# SwitchMatrix.net
KiCad netlist of a schematic drawn in Altium Designer
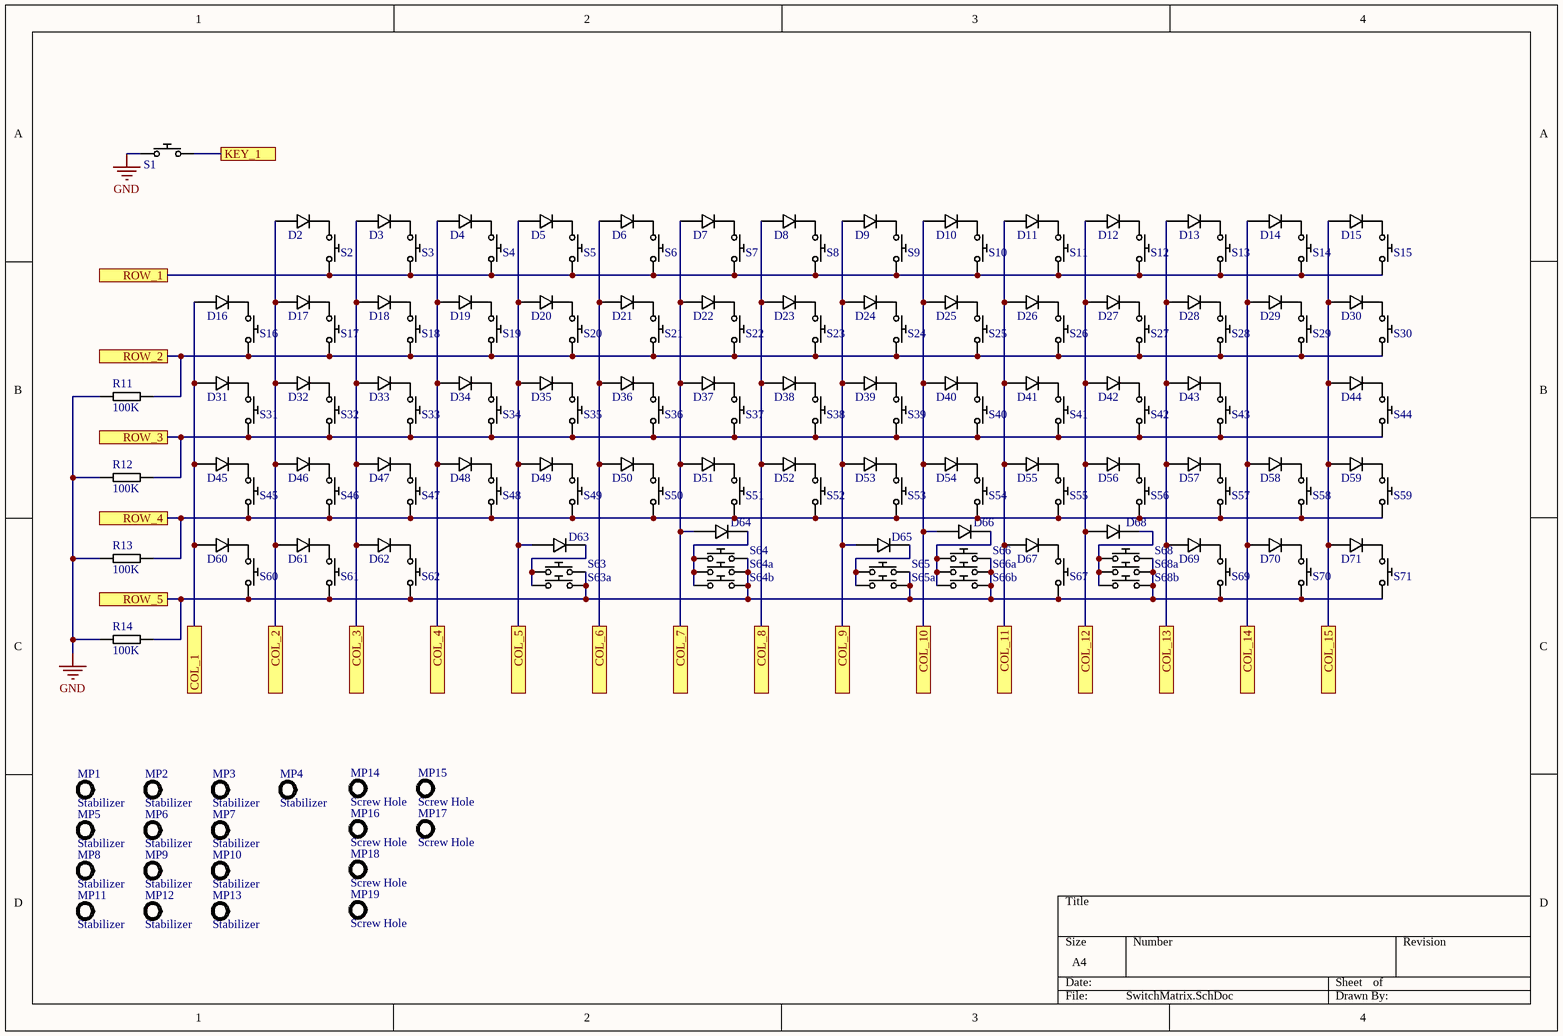
[diagram p0: SwitchMatrix.SchDoc]

(export (version "E")
  (design (tool "Eeschema 10.0.6"))
  (components
    (comp (ref "D2") (value "Diode") (footprint "SOD_323") (libsource (lib "NautilusKB") (part "Diode")))
    (comp (ref "D3") (value "Diode") (footprint "SOD_323") (libsource (lib "NautilusKB") (part "Diode")))
    (comp (ref "D4") (value "Diode") (footprint "SOD_323") (libsource (lib "NautilusKB") (part "Diode")))
    (comp (ref "D5") (value "Diode") (footprint "SOD_323") (libsource (lib "NautilusKB") (part "Diode")))
    (comp (ref "D6") (value "Diode") (footprint "SOD_323") (libsource (lib "NautilusKB") (part "Diode")))
    (comp (ref "D7") (value "Diode") (footprint "SOD_323") (libsource (lib "NautilusKB") (part "Diode")))
    (comp (ref "D8") (value "Diode") (footprint "SOD_323") (libsource (lib "NautilusKB") (part "Diode")))
    (comp (ref "D9") (value "Diode") (footprint "SOD_323") (libsource (lib "NautilusKB") (part "Diode")))
    (comp (ref "D10") (value "Diode") (footprint "SOD_323") (libsource (lib "NautilusKB") (part "Diode")))
    (comp (ref "D11") (value "Diode") (footprint "SOD_323") (libsource (lib "NautilusKB") (part "Diode")))
    (comp (ref "D12") (value "Diode") (footprint "SOD_323") (libsource (lib "NautilusKB") (part "Diode")))
    (comp (ref "D13") (value "Diode") (footprint "SOD_323") (libsource (lib "NautilusKB") (part "Diode")))
    (comp (ref "D14") (value "Diode") (footprint "SOD_323") (libsource (lib "NautilusKB") (part "Diode")))
    (comp (ref "D15") (value "Diode") (footprint "SOD_323") (libsource (lib "NautilusKB") (part "Diode")))
    (comp (ref "D16") (value "Diode") (footprint "SOD_323") (libsource (lib "NautilusKB") (part "Diode")))
    (comp (ref "D17") (value "Diode") (footprint "SOD_323") (libsource (lib "NautilusKB") (part "Diode")))
    (comp (ref "D18") (value "Diode") (footprint "SOD_323") (libsource (lib "NautilusKB") (part "Diode")))
    (comp (ref "D19") (value "Diode") (footprint "SOD_323") (libsource (lib "NautilusKB") (part "Diode")))
    (comp (ref "D20") (value "Diode") (footprint "SOD_323") (libsource (lib "NautilusKB") (part "Diode")))
    (comp (ref "D21") (value "Diode") (footprint "SOD_323") (libsource (lib "NautilusKB") (part "Diode")))
    (comp (ref "D22") (value "Diode") (footprint "SOD_323") (libsource (lib "NautilusKB") (part "Diode")))
    (comp (ref "D23") (value "Diode") (footprint "SOD_323") (libsource (lib "NautilusKB") (part "Diode")))
    (comp (ref "D24") (value "Diode") (footprint "SOD_323") (libsource (lib "NautilusKB") (part "Diode")))
    (comp (ref "D25") (value "Diode") (footprint "SOD_323") (libsource (lib "NautilusKB") (part "Diode")))
    (comp (ref "D26") (value "Diode") (footprint "SOD_323") (libsource (lib "NautilusKB") (part "Diode")))
    (comp (ref "D27") (value "Diode") (footprint "SOD_323") (libsource (lib "NautilusKB") (part "Diode")))
    (comp (ref "D28") (value "Diode") (footprint "SOD_323") (libsource (lib "NautilusKB") (part "Diode")))
    (comp (ref "D29") (value "Diode") (footprint "SOD_323") (libsource (lib "NautilusKB") (part "Diode")))
    (comp (ref "D30") (value "Diode") (footprint "SOD_323") (libsource (lib "NautilusKB") (part "Diode")))
    (comp (ref "D31") (value "Diode") (footprint "SOD_323") (libsource (lib "NautilusKB") (part "Diode")))
    (comp (ref "D32") (value "Diode") (footprint "SOD_323") (libsource (lib "NautilusKB") (part "Diode")))
    (comp (ref "D33") (value "Diode") (footprint "SOD_323") (libsource (lib "NautilusKB") (part "Diode")))
    (comp (ref "D34") (value "Diode") (footprint "SOD_323") (libsource (lib "NautilusKB") (part "Diode")))
    (comp (ref "D35") (value "Diode") (footprint "SOD_323") (libsource (lib "NautilusKB") (part "Diode")))
    (comp (ref "D36") (value "Diode") (footprint "SOD_323") (libsource (lib "NautilusKB") (part "Diode")))
    (comp (ref "D37") (value "Diode") (footprint "SOD_323") (libsource (lib "NautilusKB") (part "Diode")))
    (comp (ref "D38") (value "Diode") (footprint "SOD_323") (libsource (lib "NautilusKB") (part "Diode")))
    (comp (ref "D39") (value "Diode") (footprint "SOD_323") (libsource (lib "NautilusKB") (part "Diode")))
    (comp (ref "D40") (value "Diode") (footprint "SOD_323") (libsource (lib "NautilusKB") (part "Diode")))
    (comp (ref "D41") (value "Diode") (footprint "SOD_323") (libsource (lib "NautilusKB") (part "Diode")))
    (comp (ref "D42") (value "Diode") (footprint "SOD_323") (libsource (lib "NautilusKB") (part "Diode")))
    (comp (ref "D43") (value "Diode") (footprint "SOD_323") (libsource (lib "NautilusKB") (part "Diode")))
    (comp (ref "D44") (value "Diode") (footprint "SOD_323") (libsource (lib "NautilusKB") (part "Diode")))
    (comp (ref "D45") (value "Diode") (footprint "SOD_323") (libsource (lib "NautilusKB") (part "Diode")))
    (comp (ref "D46") (value "Diode") (footprint "SOD_323") (libsource (lib "NautilusKB") (part "Diode")))
    (comp (ref "D47") (value "Diode") (footprint "SOD_323") (libsource (lib "NautilusKB") (part "Diode")))
    (comp (ref "D48") (value "Diode") (footprint "SOD_323") (libsource (lib "NautilusKB") (part "Diode")))
    (comp (ref "D49") (value "Diode") (footprint "SOD_323") (libsource (lib "NautilusKB") (part "Diode")))
    (comp (ref "D50") (value "Diode") (footprint "SOD_323") (libsource (lib "NautilusKB") (part "Diode")))
    (comp (ref "D51") (value "Diode") (footprint "SOD_323") (libsource (lib "NautilusKB") (part "Diode")))
    (comp (ref "D52") (value "Diode") (footprint "SOD_323") (libsource (lib "NautilusKB") (part "Diode")))
    (comp (ref "D53") (value "Diode") (footprint "SOD_323") (libsource (lib "NautilusKB") (part "Diode")))
    (comp (ref "D54") (value "Diode") (footprint "SOD_323") (libsource (lib "NautilusKB") (part "Diode")))
    (comp (ref "D55") (value "Diode") (footprint "SOD_323") (libsource (lib "NautilusKB") (part "Diode")))
    (comp (ref "D56") (value "Diode") (footprint "SOD_323") (libsource (lib "NautilusKB") (part "Diode")))
    (comp (ref "D57") (value "Diode") (footprint "SOD_323") (libsource (lib "NautilusKB") (part "Diode")))
    (comp (ref "D58") (value "Diode") (footprint "SOD_323") (libsource (lib "NautilusKB") (part "Diode")))
    (comp (ref "D59") (value "Diode") (footprint "SOD_323") (libsource (lib "NautilusKB") (part "Diode")))
    (comp (ref "D60") (value "Diode") (footprint "SOD_323") (libsource (lib "NautilusKB") (part "Diode")))
    (comp (ref "D61") (value "Diode") (footprint "SOD_323") (libsource (lib "NautilusKB") (part "Diode")))
    (comp (ref "D62") (value "Diode") (footprint "SOD_323") (libsource (lib "NautilusKB") (part "Diode")))
    (comp (ref "D63") (value "Diode") (footprint "SOD_323") (libsource (lib "NautilusKB") (part "Diode")))
    (comp (ref "D64") (value "Diode") (footprint "SOD_323") (libsource (lib "NautilusKB") (part "Diode")))
    (comp (ref "D65") (value "Diode") (footprint "SOD_323") (libsource (lib "NautilusKB") (part "Diode")))
    (comp (ref "D66") (value "Diode") (footprint "SOD_323") (libsource (lib "NautilusKB") (part "Diode")))
    (comp (ref "D67") (value "Diode") (footprint "SOD_323") (libsource (lib "NautilusKB") (part "Diode")))
    (comp (ref "D68") (value "Diode") (footprint "SOD_323") (libsource (lib "NautilusKB") (part "Diode")))
    (comp (ref "D69") (value "Diode") (footprint "SOD_323") (libsource (lib "NautilusKB") (part "Diode")))
    (comp (ref "D70") (value "Diode") (footprint "SOD_323") (libsource (lib "NautilusKB") (part "Diode")))
    (comp (ref "D71") (value "Diode") (footprint "SOD_323") (libsource (lib "NautilusKB") (part "Diode")))
    (comp (ref "MP1")
      (value "Stabilizer")
      (footprint "Cherry_stabilizer")
      (libsource (lib "NautilusKB") (part "Cherry_Stabilizer"))
    )
    (comp (ref "MP2")
      (value "Stabilizer")
      (footprint "Cherry_stabilizer")
      (libsource (lib "NautilusKB") (part "Cherry_Stabilizer"))
    )
    (comp (ref "MP3")
      (value "Stabilizer")
      (footprint "Cherry_stabilizer")
      (libsource (lib "NautilusKB") (part "Cherry_Stabilizer"))
    )
    (comp (ref "MP4")
      (value "Stabilizer")
      (footprint "Cherry_stabilizer")
      (libsource (lib "NautilusKB") (part "Cherry_Stabilizer"))
    )
    (comp (ref "MP5")
      (value "Stabilizer")
      (footprint "Cherry_stabilizer")
      (libsource (lib "NautilusKB") (part "Cherry_Stabilizer"))
    )
    (comp (ref "MP6")
      (value "Stabilizer")
      (footprint "Cherry_stabilizer")
      (libsource (lib "NautilusKB") (part "Cherry_Stabilizer"))
    )
    (comp (ref "MP7")
      (value "Stabilizer")
      (footprint "Cherry_stabilizer")
      (libsource (lib "NautilusKB") (part "Cherry_Stabilizer"))
    )
    (comp (ref "MP8")
      (value "Stabilizer")
      (footprint "Cherry_stabilizer")
      (libsource (lib "NautilusKB") (part "Cherry_Stabilizer"))
    )
    (comp (ref "MP9")
      (value "Stabilizer")
      (footprint "Cherry_stabilizer")
      (libsource (lib "NautilusKB") (part "Cherry_Stabilizer"))
    )
    (comp (ref "MP10")
      (value "Stabilizer")
      (footprint "Cherry_stabilizer")
      (libsource (lib "NautilusKB") (part "Cherry_Stabilizer"))
    )
    (comp (ref "MP11")
      (value "Stabilizer")
      (footprint "Cherry_stabilizer")
      (libsource (lib "NautilusKB") (part "Cherry_Stabilizer"))
    )
    (comp (ref "MP12")
      (value "Stabilizer")
      (footprint "Cherry_stabilizer")
      (libsource (lib "NautilusKB") (part "Cherry_Stabilizer"))
    )
    (comp (ref "MP13")
      (value "Stabilizer")
      (footprint "Cherry_stabilizer")
      (libsource (lib "NautilusKB") (part "Cherry_Stabilizer"))
    )
    (comp (ref "MP14")
      (value "Screw Hole")
      (footprint "Slot_2.2x5mm")
      (libsource (lib "NautilusKB") (part "Mechanical_part"))
    )
    (comp (ref "MP15")
      (value "Screw Hole")
      (footprint "Slot_2.2x5mm")
      (libsource (lib "NautilusKB") (part "Mechanical_part"))
    )
    (comp (ref "MP16")
      (value "Screw Hole")
      (footprint "Slot_2.2x5mm")
      (libsource (lib "NautilusKB") (part "Mechanical_part"))
    )
    (comp (ref "MP17")
      (value "Screw Hole")
      (footprint "Slot_2.2x5mm")
      (libsource (lib "NautilusKB") (part "Mechanical_part"))
    )
    (comp (ref "MP18")
      (value "Screw Hole")
      (footprint "Slot_2.2x5mm")
      (libsource (lib "NautilusKB") (part "Mechanical_part"))
    )
    (comp (ref "MP19")
      (value "Screw Hole")
      (footprint "Slot_2.2x5mm")
      (libsource (lib "NautilusKB") (part "Mechanical_part"))
    )
    (comp (ref "R11")
      (value "100K")
      (footprint "Resistor_0603")
      (libsource (lib "NautilusKB") (part "Resistor"))
    )
    (comp (ref "R12")
      (value "100K")
      (footprint "Resistor_0603")
      (libsource (lib "NautilusKB") (part "Resistor"))
    )
    (comp (ref "R13")
      (value "100K")
      (footprint "Resistor_0603")
      (libsource (lib "NautilusKB") (part "Resistor"))
    )
    (comp (ref "R14")
      (value "100K")
      (footprint "Resistor_0603")
      (libsource (lib "NautilusKB") (part "Resistor"))
    )
    (comp (ref "S1")
      (value "Pushbutton_2P")
      (footprint "CherryMX_PCB_RGB")
      (libsource (lib "NautilusKB") (part "Pushbutton_2P"))
    )
    (comp (ref "S2")
      (value "Pushbutton_2P")
      (footprint "CherryMX_PCB_RGB")
      (libsource (lib "NautilusKB") (part "Pushbutton_2P"))
    )
    (comp (ref "S3")
      (value "Pushbutton_2P")
      (footprint "CherryMX_PCB_RGB")
      (libsource (lib "NautilusKB") (part "Pushbutton_2P"))
    )
    (comp (ref "S4")
      (value "Pushbutton_2P")
      (footprint "CherryMX_PCB_RGB")
      (libsource (lib "NautilusKB") (part "Pushbutton_2P"))
    )
    (comp (ref "S5")
      (value "Pushbutton_2P")
      (footprint "CherryMX_PCB_RGB")
      (libsource (lib "NautilusKB") (part "Pushbutton_2P"))
    )
    (comp (ref "S6")
      (value "Pushbutton_2P")
      (footprint "CherryMX_PCB_RGB")
      (libsource (lib "NautilusKB") (part "Pushbutton_2P"))
    )
    (comp (ref "S7")
      (value "Pushbutton_2P")
      (footprint "CherryMX_PCB_RGB")
      (libsource (lib "NautilusKB") (part "Pushbutton_2P"))
    )
    (comp (ref "S8")
      (value "Pushbutton_2P")
      (footprint "CherryMX_PCB_RGB")
      (libsource (lib "NautilusKB") (part "Pushbutton_2P"))
    )
    (comp (ref "S9")
      (value "Pushbutton_2P")
      (footprint "CherryMX_PCB_RGB")
      (libsource (lib "NautilusKB") (part "Pushbutton_2P"))
    )
    (comp (ref "S10")
      (value "Pushbutton_2P")
      (footprint "CherryMX_PCB_RGB")
      (libsource (lib "NautilusKB") (part "Pushbutton_2P"))
    )
    (comp (ref "S11")
      (value "Pushbutton_2P")
      (footprint "CherryMX_PCB_RGB")
      (libsource (lib "NautilusKB") (part "Pushbutton_2P"))
    )
    (comp (ref "S12")
      (value "Pushbutton_2P")
      (footprint "CherryMX_PCB_RGB")
      (libsource (lib "NautilusKB") (part "Pushbutton_2P"))
    )
    (comp (ref "S13")
      (value "Pushbutton_2P")
      (footprint "CherryMX_PCB_RGB")
      (libsource (lib "NautilusKB") (part "Pushbutton_2P"))
    )
    (comp (ref "S14")
      (value "Pushbutton_2P")
      (footprint "CherryMX_PCB_RGB")
      (libsource (lib "NautilusKB") (part "Pushbutton_2P"))
    )
    (comp (ref "S15")
      (value "Pushbutton_2P")
      (footprint "CherryMX_PCB_RGB")
      (libsource (lib "NautilusKB") (part "Pushbutton_2P"))
    )
    (comp (ref "S16")
      (value "Pushbutton_2P")
      (footprint "CherryMX_PCB_RGB")
      (libsource (lib "NautilusKB") (part "Pushbutton_2P"))
    )
    (comp (ref "S17")
      (value "Pushbutton_2P")
      (footprint "CherryMX_PCB_RGB")
      (libsource (lib "NautilusKB") (part "Pushbutton_2P"))
    )
    (comp (ref "S18")
      (value "Pushbutton_2P")
      (footprint "CherryMX_PCB_RGB")
      (libsource (lib "NautilusKB") (part "Pushbutton_2P"))
    )
    (comp (ref "S19")
      (value "Pushbutton_2P")
      (footprint "CherryMX_PCB_RGB")
      (libsource (lib "NautilusKB") (part "Pushbutton_2P"))
    )
    (comp (ref "S20")
      (value "Pushbutton_2P")
      (footprint "CherryMX_PCB_RGB")
      (libsource (lib "NautilusKB") (part "Pushbutton_2P"))
    )
    (comp (ref "S21")
      (value "Pushbutton_2P")
      (footprint "CherryMX_PCB_RGB")
      (libsource (lib "NautilusKB") (part "Pushbutton_2P"))
    )
    (comp (ref "S22")
      (value "Pushbutton_2P")
      (footprint "CherryMX_PCB_RGB")
      (libsource (lib "NautilusKB") (part "Pushbutton_2P"))
    )
    (comp (ref "S23")
      (value "Pushbutton_2P")
      (footprint "CherryMX_PCB_RGB")
      (libsource (lib "NautilusKB") (part "Pushbutton_2P"))
    )
    (comp (ref "S24")
      (value "Pushbutton_2P")
      (footprint "CherryMX_PCB_RGB")
      (libsource (lib "NautilusKB") (part "Pushbutton_2P"))
    )
    (comp (ref "S25")
      (value "Pushbutton_2P")
      (footprint "CherryMX_PCB_RGB")
      (libsource (lib "NautilusKB") (part "Pushbutton_2P"))
    )
    (comp (ref "S26")
      (value "Pushbutton_2P")
      (footprint "CherryMX_PCB_RGB")
      (libsource (lib "NautilusKB") (part "Pushbutton_2P"))
    )
    (comp (ref "S27")
      (value "Pushbutton_2P")
      (footprint "CherryMX_PCB_RGB")
      (libsource (lib "NautilusKB") (part "Pushbutton_2P"))
    )
    (comp (ref "S28")
      (value "Pushbutton_2P")
      (footprint "CherryMX_PCB_RGB")
      (libsource (lib "NautilusKB") (part "Pushbutton_2P"))
    )
    (comp (ref "S29")
      (value "Pushbutton_2P")
      (footprint "CherryMX_PCB_RGB")
      (libsource (lib "NautilusKB") (part "Pushbutton_2P"))
    )
    (comp (ref "S30")
      (value "Pushbutton_2P")
      (footprint "CherryMX_PCB_RGB")
      (libsource (lib "NautilusKB") (part "Pushbutton_2P"))
    )
    (comp (ref "S31")
      (value "Pushbutton_2P")
      (footprint "CherryMX_PCB_RGB")
      (libsource (lib "NautilusKB") (part "Pushbutton_2P"))
    )
    (comp (ref "S32")
      (value "Pushbutton_2P")
      (footprint "CherryMX_PCB_RGB")
      (libsource (lib "NautilusKB") (part "Pushbutton_2P"))
    )
    (comp (ref "S33")
      (value "Pushbutton_2P")
      (footprint "CherryMX_PCB_RGB")
      (libsource (lib "NautilusKB") (part "Pushbutton_2P"))
    )
    (comp (ref "S34")
      (value "Pushbutton_2P")
      (footprint "CherryMX_PCB_RGB")
      (libsource (lib "NautilusKB") (part "Pushbutton_2P"))
    )
    (comp (ref "S35")
      (value "Pushbutton_2P")
      (footprint "CherryMX_PCB_RGB")
      (libsource (lib "NautilusKB") (part "Pushbutton_2P"))
    )
    (comp (ref "S36")
      (value "Pushbutton_2P")
      (footprint "CherryMX_PCB_RGB")
      (libsource (lib "NautilusKB") (part "Pushbutton_2P"))
    )
    (comp (ref "S37")
      (value "Pushbutton_2P")
      (footprint "CherryMX_PCB_RGB")
      (libsource (lib "NautilusKB") (part "Pushbutton_2P"))
    )
    (comp (ref "S38")
      (value "Pushbutton_2P")
      (footprint "CherryMX_PCB_RGB")
      (libsource (lib "NautilusKB") (part "Pushbutton_2P"))
    )
    (comp (ref "S39")
      (value "Pushbutton_2P")
      (footprint "CherryMX_PCB_RGB")
      (libsource (lib "NautilusKB") (part "Pushbutton_2P"))
    )
    (comp (ref "S40")
      (value "Pushbutton_2P")
      (footprint "CherryMX_PCB_RGB")
      (libsource (lib "NautilusKB") (part "Pushbutton_2P"))
    )
    (comp (ref "S41")
      (value "Pushbutton_2P")
      (footprint "CherryMX_PCB_RGB")
      (libsource (lib "NautilusKB") (part "Pushbutton_2P"))
    )
    (comp (ref "S42")
      (value "Pushbutton_2P")
      (footprint "CherryMX_PCB_RGB")
      (libsource (lib "NautilusKB") (part "Pushbutton_2P"))
    )
    (comp (ref "S43")
      (value "Pushbutton_2P")
      (footprint "CherryMX_PCB_RGB")
      (libsource (lib "NautilusKB") (part "Pushbutton_2P"))
    )
    (comp (ref "S44")
      (value "Pushbutton_2P")
      (footprint "CherryMX_PCB_RGB")
      (libsource (lib "NautilusKB") (part "Pushbutton_2P"))
    )
    (comp (ref "S45")
      (value "Pushbutton_2P")
      (footprint "CherryMX_PCB_RGB")
      (libsource (lib "NautilusKB") (part "Pushbutton_2P"))
    )
    (comp (ref "S46")
      (value "Pushbutton_2P")
      (footprint "CherryMX_PCB_RGB")
      (libsource (lib "NautilusKB") (part "Pushbutton_2P"))
    )
    (comp (ref "S47")
      (value "Pushbutton_2P")
      (footprint "CherryMX_PCB_RGB")
      (libsource (lib "NautilusKB") (part "Pushbutton_2P"))
    )
    (comp (ref "S48")
      (value "Pushbutton_2P")
      (footprint "CherryMX_PCB_RGB")
      (libsource (lib "NautilusKB") (part "Pushbutton_2P"))
    )
    (comp (ref "S49")
      (value "Pushbutton_2P")
      (footprint "CherryMX_PCB_RGB")
      (libsource (lib "NautilusKB") (part "Pushbutton_2P"))
    )
    (comp (ref "S50")
      (value "Pushbutton_2P")
      (footprint "CherryMX_PCB_RGB")
      (libsource (lib "NautilusKB") (part "Pushbutton_2P"))
    )
    (comp (ref "S51")
      (value "Pushbutton_2P")
      (footprint "CherryMX_PCB_RGB")
      (libsource (lib "NautilusKB") (part "Pushbutton_2P"))
    )
    (comp (ref "S52")
      (value "Pushbutton_2P")
      (footprint "CherryMX_PCB_RGB")
      (libsource (lib "NautilusKB") (part "Pushbutton_2P"))
    )
    (comp (ref "S53")
      (value "Pushbutton_2P")
      (footprint "CherryMX_PCB_RGB")
      (libsource (lib "NautilusKB") (part "Pushbutton_2P"))
    )
    (comp (ref "S54")
      (value "Pushbutton_2P")
      (footprint "CherryMX_PCB_RGB")
      (libsource (lib "NautilusKB") (part "Pushbutton_2P"))
    )
    (comp (ref "S55")
      (value "Pushbutton_2P")
      (footprint "CherryMX_PCB_RGB")
      (libsource (lib "NautilusKB") (part "Pushbutton_2P"))
    )
    (comp (ref "S56")
      (value "Pushbutton_2P")
      (footprint "CherryMX_PCB_RGB")
      (libsource (lib "NautilusKB") (part "Pushbutton_2P"))
    )
    (comp (ref "S57")
      (value "Pushbutton_2P")
      (footprint "CherryMX_PCB_RGB")
      (libsource (lib "NautilusKB") (part "Pushbutton_2P"))
    )
    (comp (ref "S58")
      (value "Pushbutton_2P")
      (footprint "CherryMX_PCB_RGB")
      (libsource (lib "NautilusKB") (part "Pushbutton_2P"))
    )
    (comp (ref "S59")
      (value "Pushbutton_2P")
      (footprint "CherryMX_PCB_RGB")
      (libsource (lib "NautilusKB") (part "Pushbutton_2P"))
    )
    (comp (ref "S60")
      (value "Pushbutton_2P")
      (footprint "CherryMX_PCB_RGB")
      (libsource (lib "NautilusKB") (part "Pushbutton_2P"))
    )
    (comp (ref "S61")
      (value "Pushbutton_2P")
      (footprint "CherryMX_PCB_RGB")
      (libsource (lib "NautilusKB") (part "Pushbutton_2P"))
    )
    (comp (ref "S62")
      (value "Pushbutton_2P")
      (footprint "CherryMX_PCB_RGB")
      (libsource (lib "NautilusKB") (part "Pushbutton_2P"))
    )
    (comp (ref "S63")
      (value "Pushbutton_2P")
      (footprint "CherryMX_PCB_RGB")
      (libsource (lib "NautilusKB") (part "Pushbutton_2P"))
    )
    (comp (ref "S63a")
      (value "Pushbutton_2P")
      (footprint "CherryMX_PCB_RGB")
      (libsource (lib "NautilusKB") (part "Pushbutton_2P"))
    )
    (comp (ref "S64")
      (value "Pushbutton_2P")
      (footprint "CherryMX_PCB_RGB")
      (libsource (lib "NautilusKB") (part "Pushbutton_2P"))
    )
    (comp (ref "S64a")
      (value "Comment")
      (footprint "CherryMX_PCB_RGB")
      (libsource (lib "NautilusKB") (part "Pushbutton_2P"))
    )
    (comp (ref "S64b")
      (value "Comment")
      (footprint "CherryMX_PCB_RGB")
      (libsource (lib "NautilusKB") (part "Pushbutton_2P"))
    )
    (comp (ref "S65")
      (value "Pushbutton_2P")
      (footprint "CherryMX_PCB_RGB")
      (libsource (lib "NautilusKB") (part "Pushbutton_2P"))
    )
    (comp (ref "S65a")
      (value "Comment")
      (footprint "CherryMX_PCB_RGB")
      (libsource (lib "NautilusKB") (part "Pushbutton_2P"))
    )
    (comp (ref "S66")
      (value "Pushbutton_2P")
      (footprint "CherryMX_PCB_RGB")
      (libsource (lib "NautilusKB") (part "Pushbutton_2P"))
    )
    (comp (ref "S66a")
      (value "Comment")
      (footprint "CherryMX_PCB_RGB")
      (libsource (lib "NautilusKB") (part "Pushbutton_2P"))
    )
    (comp (ref "S66b")
      (value "Comment")
      (footprint "CherryMX_PCB_RGB")
      (libsource (lib "NautilusKB") (part "Pushbutton_2P"))
    )
    (comp (ref "S67")
      (value "Comment")
      (footprint "CherryMX_PCB_RGB")
      (libsource (lib "NautilusKB") (part "Pushbutton_2P"))
    )
    (comp (ref "S68")
      (value "Pushbutton_2P")
      (footprint "CherryMX_PCB_RGB")
      (libsource (lib "NautilusKB") (part "Pushbutton_2P"))
    )
    (comp (ref "S68a")
      (value "Comment")
      (footprint "CherryMX_PCB_RGB")
      (libsource (lib "NautilusKB") (part "Pushbutton_2P"))
    )
    (comp (ref "S68b")
      (value "Comment")
      (footprint "CherryMX_PCB_RGB")
      (libsource (lib "NautilusKB") (part "Pushbutton_2P"))
    )
    (comp (ref "S69")
      (value "Pushbutton_2P")
      (footprint "CherryMX_PCB_RGB")
      (libsource (lib "NautilusKB") (part "Pushbutton_2P"))
    )
    (comp (ref "S70")
      (value "Pushbutton_2P")
      (footprint "CherryMX_PCB_RGB")
      (libsource (lib "NautilusKB") (part "Pushbutton_2P"))
    )
    (comp (ref "S71")
      (value "Pushbutton_2P")
      (footprint "CherryMX_PCB_RGB")
      (libsource (lib "NautilusKB") (part "Pushbutton_2P"))
    )
  )
  (nets
    (net (code "1") (name "/COL_1") (class "Default")
      (node (ref "D16") (pin "A") (pintype "passive"))
      (node (ref "D31") (pin "A") (pintype "passive"))
      (node (ref "D45") (pin "A") (pintype "passive"))
      (node (ref "D60") (pin "A") (pintype "passive"))
    )
    (net (code "2") (name "/COL_2") (class "Default")
      (node (ref "D17") (pin "A") (pintype "passive"))
      (node (ref "D2") (pin "A") (pintype "passive"))
      (node (ref "D32") (pin "A") (pintype "passive"))
      (node (ref "D46") (pin "A") (pintype "passive"))
      (node (ref "D61") (pin "A") (pintype "passive"))
    )
    (net (code "3") (name "/COL_3") (class "Default")
      (node (ref "D18") (pin "A") (pintype "passive"))
      (node (ref "D3") (pin "A") (pintype "passive"))
      (node (ref "D33") (pin "A") (pintype "passive"))
      (node (ref "D47") (pin "A") (pintype "passive"))
      (node (ref "D62") (pin "A") (pintype "passive"))
    )
    (net (code "4") (name "/COL_4") (class "Default")
      (node (ref "D19") (pin "A") (pintype "passive"))
      (node (ref "D34") (pin "A") (pintype "passive"))
      (node (ref "D4") (pin "A") (pintype "passive"))
      (node (ref "D48") (pin "A") (pintype "passive"))
    )
    (net (code "5") (name "/COL_5") (class "Default")
      (node (ref "D20") (pin "A") (pintype "passive"))
      (node (ref "D35") (pin "A") (pintype "passive"))
      (node (ref "D49") (pin "A") (pintype "passive"))
      (node (ref "D5") (pin "A") (pintype "passive"))
      (node (ref "D63") (pin "A") (pintype "passive"))
    )
    (net (code "6") (name "/COL_6") (class "Default")
      (node (ref "D21") (pin "A") (pintype "passive"))
      (node (ref "D36") (pin "A") (pintype "passive"))
      (node (ref "D50") (pin "A") (pintype "passive"))
      (node (ref "D6") (pin "A") (pintype "passive"))
    )
    (net (code "7") (name "/COL_7") (class "Default")
      (node (ref "D22") (pin "A") (pintype "passive"))
      (node (ref "D37") (pin "A") (pintype "passive"))
      (node (ref "D51") (pin "A") (pintype "passive"))
      (node (ref "D64") (pin "A") (pintype "passive"))
      (node (ref "D7") (pin "A") (pintype "passive"))
    )
    (net (code "8") (name "/COL_8") (class "Default")
      (node (ref "D23") (pin "A") (pintype "passive"))
      (node (ref "D38") (pin "A") (pintype "passive"))
      (node (ref "D52") (pin "A") (pintype "passive"))
      (node (ref "D8") (pin "A") (pintype "passive"))
    )
    (net (code "9") (name "/COL_9") (class "Default")
      (node (ref "D24") (pin "A") (pintype "passive"))
      (node (ref "D39") (pin "A") (pintype "passive"))
      (node (ref "D53") (pin "A") (pintype "passive"))
      (node (ref "D65") (pin "A") (pintype "passive"))
      (node (ref "D9") (pin "A") (pintype "passive"))
    )
    (net (code "10") (name "/COL_10") (class "Default")
      (node (ref "D10") (pin "A") (pintype "passive"))
      (node (ref "D25") (pin "A") (pintype "passive"))
      (node (ref "D40") (pin "A") (pintype "passive"))
      (node (ref "D54") (pin "A") (pintype "passive"))
      (node (ref "D66") (pin "A") (pintype "passive"))
    )
    (net (code "11") (name "/COL_11") (class "Default")
      (node (ref "D11") (pin "A") (pintype "passive"))
      (node (ref "D26") (pin "A") (pintype "passive"))
      (node (ref "D41") (pin "A") (pintype "passive"))
      (node (ref "D55") (pin "A") (pintype "passive"))
      (node (ref "D67") (pin "A") (pintype "passive"))
    )
    (net (code "12") (name "/COL_12") (class "Default")
      (node (ref "D12") (pin "A") (pintype "passive"))
      (node (ref "D27") (pin "A") (pintype "passive"))
      (node (ref "D42") (pin "A") (pintype "passive"))
      (node (ref "D56") (pin "A") (pintype "passive"))
      (node (ref "D68") (pin "A") (pintype "passive"))
    )
    (net (code "13") (name "/COL_13") (class "Default")
      (node (ref "D13") (pin "A") (pintype "passive"))
      (node (ref "D28") (pin "A") (pintype "passive"))
      (node (ref "D43") (pin "A") (pintype "passive"))
      (node (ref "D57") (pin "A") (pintype "passive"))
      (node (ref "D69") (pin "A") (pintype "passive"))
    )
    (net (code "14") (name "/COL_14") (class "Default")
      (node (ref "D14") (pin "A") (pintype "passive"))
      (node (ref "D29") (pin "A") (pintype "passive"))
      (node (ref "D58") (pin "A") (pintype "passive"))
      (node (ref "D70") (pin "A") (pintype "passive"))
    )
    (net (code "15") (name "/COL_15") (class "Default")
      (node (ref "D15") (pin "A") (pintype "passive"))
      (node (ref "D30") (pin "A") (pintype "passive"))
      (node (ref "D44") (pin "A") (pintype "passive"))
      (node (ref "D59") (pin "A") (pintype "passive"))
      (node (ref "D71") (pin "A") (pintype "passive"))
    )
    (net (code "16") (name "/KEY_1") (class "Default") (node (ref "S1") (pin "2") (pintype "passive")))
    (net (code "17") (name "/ROW_1") (class "Default")
      (node (ref "S10") (pin "2") (pintype "passive"))
      (node (ref "S11") (pin "2") (pintype "passive"))
      (node (ref "S12") (pin "2") (pintype "passive"))
      (node (ref "S13") (pin "2") (pintype "passive"))
      (node (ref "S14") (pin "2") (pintype "passive"))
      (node (ref "S15") (pin "2") (pintype "passive"))
      (node (ref "S2") (pin "2") (pintype "passive"))
      (node (ref "S3") (pin "2") (pintype "passive"))
      (node (ref "S4") (pin "2") (pintype "passive"))
      (node (ref "S5") (pin "2") (pintype "passive"))
      (node (ref "S6") (pin "2") (pintype "passive"))
      (node (ref "S7") (pin "2") (pintype "passive"))
      (node (ref "S8") (pin "2") (pintype "passive"))
      (node (ref "S9") (pin "2") (pintype "passive"))
    )
    (net (code "18") (name "/ROW_2") (class "Default")
      (node (ref "R11") (pin "2") (pintype "passive"))
      (node (ref "S16") (pin "2") (pintype "passive"))
      (node (ref "S17") (pin "2") (pintype "passive"))
      (node (ref "S18") (pin "2") (pintype "passive"))
      (node (ref "S19") (pin "2") (pintype "passive"))
      (node (ref "S20") (pin "2") (pintype "passive"))
      (node (ref "S21") (pin "2") (pintype "passive"))
      (node (ref "S22") (pin "2") (pintype "passive"))
      (node (ref "S23") (pin "2") (pintype "passive"))
      (node (ref "S24") (pin "2") (pintype "passive"))
      (node (ref "S25") (pin "2") (pintype "passive"))
      (node (ref "S26") (pin "2") (pintype "passive"))
      (node (ref "S27") (pin "2") (pintype "passive"))
      (node (ref "S28") (pin "2") (pintype "passive"))
      (node (ref "S29") (pin "2") (pintype "passive"))
      (node (ref "S30") (pin "2") (pintype "passive"))
    )
    (net (code "19") (name "/ROW_3") (class "Default")
      (node (ref "R12") (pin "2") (pintype "passive"))
      (node (ref "S31") (pin "2") (pintype "passive"))
      (node (ref "S32") (pin "2") (pintype "passive"))
      (node (ref "S33") (pin "2") (pintype "passive"))
      (node (ref "S34") (pin "2") (pintype "passive"))
      (node (ref "S35") (pin "2") (pintype "passive"))
      (node (ref "S36") (pin "2") (pintype "passive"))
      (node (ref "S37") (pin "2") (pintype "passive"))
      (node (ref "S38") (pin "2") (pintype "passive"))
      (node (ref "S39") (pin "2") (pintype "passive"))
      (node (ref "S40") (pin "2") (pintype "passive"))
      (node (ref "S41") (pin "2") (pintype "passive"))
      (node (ref "S42") (pin "2") (pintype "passive"))
      (node (ref "S43") (pin "2") (pintype "passive"))
      (node (ref "S44") (pin "2") (pintype "passive"))
    )
    (net (code "20") (name "/ROW_4") (class "Default")
      (node (ref "R13") (pin "2") (pintype "passive"))
      (node (ref "S45") (pin "2") (pintype "passive"))
      (node (ref "S46") (pin "2") (pintype "passive"))
      (node (ref "S47") (pin "2") (pintype "passive"))
      (node (ref "S48") (pin "2") (pintype "passive"))
      (node (ref "S49") (pin "2") (pintype "passive"))
      (node (ref "S50") (pin "2") (pintype "passive"))
      (node (ref "S51") (pin "2") (pintype "passive"))
      (node (ref "S52") (pin "2") (pintype "passive"))
      (node (ref "S53") (pin "2") (pintype "passive"))
      (node (ref "S54") (pin "2") (pintype "passive"))
      (node (ref "S55") (pin "2") (pintype "passive"))
      (node (ref "S56") (pin "2") (pintype "passive"))
      (node (ref "S57") (pin "2") (pintype "passive"))
      (node (ref "S58") (pin "2") (pintype "passive"))
      (node (ref "S59") (pin "2") (pintype "passive"))
    )
    (net (code "21") (name "/ROW_5") (class "Default")
      (node (ref "R14") (pin "2") (pintype "passive"))
      (node (ref "S60") (pin "2") (pintype "passive"))
      (node (ref "S61") (pin "2") (pintype "passive"))
      (node (ref "S62") (pin "2") (pintype "passive"))
      (node (ref "S63") (pin "2") (pintype "passive"))
      (node (ref "S63a") (pin "2") (pintype "passive"))
      (node (ref "S64") (pin "2") (pintype "passive"))
      (node (ref "S64a") (pin "2") (pintype "passive"))
      (node (ref "S64b") (pin "2") (pintype "passive"))
      (node (ref "S65") (pin "2") (pintype "passive"))
      (node (ref "S65a") (pin "2") (pintype "passive"))
      (node (ref "S66") (pin "2") (pintype "passive"))
      (node (ref "S66a") (pin "2") (pintype "passive"))
      (node (ref "S66b") (pin "2") (pintype "passive"))
      (node (ref "S67") (pin "2") (pintype "passive"))
      (node (ref "S68") (pin "2") (pintype "passive"))
      (node (ref "S68a") (pin "2") (pintype "passive"))
      (node (ref "S68b") (pin "2") (pintype "passive"))
      (node (ref "S69") (pin "2") (pintype "passive"))
      (node (ref "S70") (pin "2") (pintype "passive"))
      (node (ref "S71") (pin "2") (pintype "passive"))
    )
    (net (code "22") (name "GND") (class "Default")
      (node (ref "R11") (pin "1") (pintype "passive"))
      (node (ref "R12") (pin "1") (pintype "passive"))
      (node (ref "R13") (pin "1") (pintype "passive"))
      (node (ref "R14") (pin "1") (pintype "passive"))
      (node (ref "S1") (pin "1") (pintype "passive"))
    )
    (net (code "23") (name "Net-(D2-PadK)") (class "Default")
      (node (ref "D2") (pin "K") (pintype "passive"))
      (node (ref "S2") (pin "1") (pintype "passive"))
    )
    (net (code "24") (name "Net-(D3-PadK)") (class "Default")
      (node (ref "D3") (pin "K") (pintype "passive"))
      (node (ref "S3") (pin "1") (pintype "passive"))
    )
    (net (code "25") (name "Net-(D4-PadK)") (class "Default")
      (node (ref "D4") (pin "K") (pintype "passive"))
      (node (ref "S4") (pin "1") (pintype "passive"))
    )
    (net (code "26") (name "Net-(D5-PadK)") (class "Default")
      (node (ref "D5") (pin "K") (pintype "passive"))
      (node (ref "S5") (pin "1") (pintype "passive"))
    )
    (net (code "27") (name "Net-(D6-PadK)") (class "Default")
      (node (ref "D6") (pin "K") (pintype "passive"))
      (node (ref "S6") (pin "1") (pintype "passive"))
    )
    (net (code "28") (name "Net-(D7-PadK)") (class "Default")
      (node (ref "D7") (pin "K") (pintype "passive"))
      (node (ref "S7") (pin "1") (pintype "passive"))
    )
    (net (code "29") (name "Net-(D8-PadK)") (class "Default")
      (node (ref "D8") (pin "K") (pintype "passive"))
      (node (ref "S8") (pin "1") (pintype "passive"))
    )
    (net (code "30") (name "Net-(D9-PadK)") (class "Default")
      (node (ref "D9") (pin "K") (pintype "passive"))
      (node (ref "S9") (pin "1") (pintype "passive"))
    )
    (net (code "31") (name "Net-(D10-PadK)") (class "Default")
      (node (ref "D10") (pin "K") (pintype "passive"))
      (node (ref "S10") (pin "1") (pintype "passive"))
    )
    (net (code "32") (name "Net-(D11-PadK)") (class "Default")
      (node (ref "D11") (pin "K") (pintype "passive"))
      (node (ref "S11") (pin "1") (pintype "passive"))
    )
    (net (code "33") (name "Net-(D12-PadK)") (class "Default")
      (node (ref "D12") (pin "K") (pintype "passive"))
      (node (ref "S12") (pin "1") (pintype "passive"))
    )
    (net (code "34") (name "Net-(D13-PadK)") (class "Default")
      (node (ref "D13") (pin "K") (pintype "passive"))
      (node (ref "S13") (pin "1") (pintype "passive"))
    )
    (net (code "35") (name "Net-(D14-PadK)") (class "Default")
      (node (ref "D14") (pin "K") (pintype "passive"))
      (node (ref "S14") (pin "1") (pintype "passive"))
    )
    (net (code "36") (name "Net-(D15-PadK)") (class "Default")
      (node (ref "D15") (pin "K") (pintype "passive"))
      (node (ref "S15") (pin "1") (pintype "passive"))
    )
    (net (code "37") (name "Net-(D16-PadK)") (class "Default")
      (node (ref "D16") (pin "K") (pintype "passive"))
      (node (ref "S16") (pin "1") (pintype "passive"))
    )
    (net (code "38") (name "Net-(D17-PadK)") (class "Default")
      (node (ref "D17") (pin "K") (pintype "passive"))
      (node (ref "S17") (pin "1") (pintype "passive"))
    )
    (net (code "39") (name "Net-(D18-PadK)") (class "Default")
      (node (ref "D18") (pin "K") (pintype "passive"))
      (node (ref "S18") (pin "1") (pintype "passive"))
    )
    (net (code "40") (name "Net-(D19-PadK)") (class "Default")
      (node (ref "D19") (pin "K") (pintype "passive"))
      (node (ref "S19") (pin "1") (pintype "passive"))
    )
    (net (code "41") (name "Net-(D20-PadK)") (class "Default")
      (node (ref "D20") (pin "K") (pintype "passive"))
      (node (ref "S20") (pin "1") (pintype "passive"))
    )
    (net (code "42") (name "Net-(D21-PadK)") (class "Default")
      (node (ref "D21") (pin "K") (pintype "passive"))
      (node (ref "S21") (pin "1") (pintype "passive"))
    )
    (net (code "43") (name "Net-(D22-PadK)") (class "Default")
      (node (ref "D22") (pin "K") (pintype "passive"))
      (node (ref "S22") (pin "1") (pintype "passive"))
    )
    (net (code "44") (name "Net-(D23-PadK)") (class "Default")
      (node (ref "D23") (pin "K") (pintype "passive"))
      (node (ref "S23") (pin "1") (pintype "passive"))
    )
    (net (code "45") (name "Net-(D24-PadK)") (class "Default")
      (node (ref "D24") (pin "K") (pintype "passive"))
      (node (ref "S24") (pin "1") (pintype "passive"))
    )
    (net (code "46") (name "Net-(D25-PadK)") (class "Default")
      (node (ref "D25") (pin "K") (pintype "passive"))
      (node (ref "S25") (pin "1") (pintype "passive"))
    )
    (net (code "47") (name "Net-(D26-PadK)") (class "Default")
      (node (ref "D26") (pin "K") (pintype "passive"))
      (node (ref "S26") (pin "1") (pintype "passive"))
    )
    (net (code "48") (name "Net-(D27-PadK)") (class "Default")
      (node (ref "D27") (pin "K") (pintype "passive"))
      (node (ref "S27") (pin "1") (pintype "passive"))
    )
    (net (code "49") (name "Net-(D28-PadK)") (class "Default")
      (node (ref "D28") (pin "K") (pintype "passive"))
      (node (ref "S28") (pin "1") (pintype "passive"))
    )
    (net (code "50") (name "Net-(D29-PadK)") (class "Default")
      (node (ref "D29") (pin "K") (pintype "passive"))
      (node (ref "S29") (pin "1") (pintype "passive"))
    )
    (net (code "51") (name "Net-(D30-PadK)") (class "Default")
      (node (ref "D30") (pin "K") (pintype "passive"))
      (node (ref "S30") (pin "1") (pintype "passive"))
    )
    (net (code "52") (name "Net-(D31-PadK)") (class "Default")
      (node (ref "D31") (pin "K") (pintype "passive"))
      (node (ref "S31") (pin "1") (pintype "passive"))
    )
    (net (code "53") (name "Net-(D32-PadK)") (class "Default")
      (node (ref "D32") (pin "K") (pintype "passive"))
      (node (ref "S32") (pin "1") (pintype "passive"))
    )
    (net (code "54") (name "Net-(D33-PadK)") (class "Default")
      (node (ref "D33") (pin "K") (pintype "passive"))
      (node (ref "S33") (pin "1") (pintype "passive"))
    )
    (net (code "55") (name "Net-(D34-PadK)") (class "Default")
      (node (ref "D34") (pin "K") (pintype "passive"))
      (node (ref "S34") (pin "1") (pintype "passive"))
    )
    (net (code "56") (name "Net-(D35-PadK)") (class "Default")
      (node (ref "D35") (pin "K") (pintype "passive"))
      (node (ref "S35") (pin "1") (pintype "passive"))
    )
    (net (code "57") (name "Net-(D36-PadK)") (class "Default")
      (node (ref "D36") (pin "K") (pintype "passive"))
      (node (ref "S36") (pin "1") (pintype "passive"))
    )
    (net (code "58") (name "Net-(D37-PadK)") (class "Default")
      (node (ref "D37") (pin "K") (pintype "passive"))
      (node (ref "S37") (pin "1") (pintype "passive"))
    )
    (net (code "59") (name "Net-(D38-PadK)") (class "Default")
      (node (ref "D38") (pin "K") (pintype "passive"))
      (node (ref "S38") (pin "1") (pintype "passive"))
    )
    (net (code "60") (name "Net-(D39-PadK)") (class "Default")
      (node (ref "D39") (pin "K") (pintype "passive"))
      (node (ref "S39") (pin "1") (pintype "passive"))
    )
    (net (code "61") (name "Net-(D40-PadK)") (class "Default")
      (node (ref "D40") (pin "K") (pintype "passive"))
      (node (ref "S40") (pin "1") (pintype "passive"))
    )
    (net (code "62") (name "Net-(D41-PadK)") (class "Default")
      (node (ref "D41") (pin "K") (pintype "passive"))
      (node (ref "S41") (pin "1") (pintype "passive"))
    )
    (net (code "63") (name "Net-(D42-PadK)") (class "Default")
      (node (ref "D42") (pin "K") (pintype "passive"))
      (node (ref "S42") (pin "1") (pintype "passive"))
    )
    (net (code "64") (name "Net-(D43-PadK)") (class "Default")
      (node (ref "D43") (pin "K") (pintype "passive"))
      (node (ref "S43") (pin "1") (pintype "passive"))
    )
    (net (code "65") (name "Net-(D44-PadK)") (class "Default")
      (node (ref "D44") (pin "K") (pintype "passive"))
      (node (ref "S44") (pin "1") (pintype "passive"))
    )
    (net (code "66") (name "Net-(D45-PadK)") (class "Default")
      (node (ref "D45") (pin "K") (pintype "passive"))
      (node (ref "S45") (pin "1") (pintype "passive"))
    )
    (net (code "67") (name "Net-(D46-PadK)") (class "Default")
      (node (ref "D46") (pin "K") (pintype "passive"))
      (node (ref "S46") (pin "1") (pintype "passive"))
    )
    (net (code "68") (name "Net-(D47-PadK)") (class "Default")
      (node (ref "D47") (pin "K") (pintype "passive"))
      (node (ref "S47") (pin "1") (pintype "passive"))
    )
    (net (code "69") (name "Net-(D48-PadK)") (class "Default")
      (node (ref "D48") (pin "K") (pintype "passive"))
      (node (ref "S48") (pin "1") (pintype "passive"))
    )
    (net (code "70") (name "Net-(D49-PadK)") (class "Default")
      (node (ref "D49") (pin "K") (pintype "passive"))
      (node (ref "S49") (pin "1") (pintype "passive"))
    )
    (net (code "71") (name "Net-(D50-PadK)") (class "Default")
      (node (ref "D50") (pin "K") (pintype "passive"))
      (node (ref "S50") (pin "1") (pintype "passive"))
    )
    (net (code "72") (name "Net-(D51-PadK)") (class "Default")
      (node (ref "D51") (pin "K") (pintype "passive"))
      (node (ref "S51") (pin "1") (pintype "passive"))
    )
    (net (code "73") (name "Net-(D52-PadK)") (class "Default")
      (node (ref "D52") (pin "K") (pintype "passive"))
      (node (ref "S52") (pin "1") (pintype "passive"))
    )
    (net (code "74") (name "Net-(D53-PadK)") (class "Default")
      (node (ref "D53") (pin "K") (pintype "passive"))
      (node (ref "S53") (pin "1") (pintype "passive"))
    )
    (net (code "75") (name "Net-(D54-PadK)") (class "Default")
      (node (ref "D54") (pin "K") (pintype "passive"))
      (node (ref "S54") (pin "1") (pintype "passive"))
    )
    (net (code "76") (name "Net-(D55-PadK)") (class "Default")
      (node (ref "D55") (pin "K") (pintype "passive"))
      (node (ref "S55") (pin "1") (pintype "passive"))
    )
    (net (code "77") (name "Net-(D56-PadK)") (class "Default")
      (node (ref "D56") (pin "K") (pintype "passive"))
      (node (ref "S56") (pin "1") (pintype "passive"))
    )
    (net (code "78") (name "Net-(D57-PadK)") (class "Default")
      (node (ref "D57") (pin "K") (pintype "passive"))
      (node (ref "S57") (pin "1") (pintype "passive"))
    )
    (net (code "79") (name "Net-(D58-PadK)") (class "Default")
      (node (ref "D58") (pin "K") (pintype "passive"))
      (node (ref "S58") (pin "1") (pintype "passive"))
    )
    (net (code "80") (name "Net-(D59-PadK)") (class "Default")
      (node (ref "D59") (pin "K") (pintype "passive"))
      (node (ref "S59") (pin "1") (pintype "passive"))
    )
    (net (code "81") (name "Net-(D60-PadK)") (class "Default")
      (node (ref "D60") (pin "K") (pintype "passive"))
      (node (ref "S60") (pin "1") (pintype "passive"))
    )
    (net (code "82") (name "Net-(D61-PadK)") (class "Default")
      (node (ref "D61") (pin "K") (pintype "passive"))
      (node (ref "S61") (pin "1") (pintype "passive"))
    )
    (net (code "83") (name "Net-(D62-PadK)") (class "Default")
      (node (ref "D62") (pin "K") (pintype "passive"))
      (node (ref "S62") (pin "1") (pintype "passive"))
    )
    (net (code "84") (name "Net-(D63-PadK)") (class "Default")
      (node (ref "D63") (pin "K") (pintype "passive"))
      (node (ref "S63") (pin "1") (pintype "passive"))
      (node (ref "S63a") (pin "1") (pintype "passive"))
    )
    (net (code "85") (name "Net-(D64-PadK)") (class "Default")
      (node (ref "D64") (pin "K") (pintype "passive"))
      (node (ref "S64") (pin "1") (pintype "passive"))
      (node (ref "S64a") (pin "1") (pintype "passive"))
      (node (ref "S64b") (pin "1") (pintype "passive"))
    )
    (net (code "86") (name "Net-(D65-PadK)") (class "Default")
      (node (ref "D65") (pin "K") (pintype "passive"))
      (node (ref "S65") (pin "1") (pintype "passive"))
      (node (ref "S65a") (pin "1") (pintype "passive"))
    )
    (net (code "87") (name "Net-(D66-PadK)") (class "Default")
      (node (ref "D66") (pin "K") (pintype "passive"))
      (node (ref "S66") (pin "1") (pintype "passive"))
      (node (ref "S66a") (pin "1") (pintype "passive"))
      (node (ref "S66b") (pin "1") (pintype "passive"))
    )
    (net (code "88") (name "Net-(D67-PadK)") (class "Default")
      (node (ref "D67") (pin "K") (pintype "passive"))
      (node (ref "S67") (pin "1") (pintype "passive"))
    )
    (net (code "89") (name "Net-(D68-PadK)") (class "Default")
      (node (ref "D68") (pin "K") (pintype "passive"))
      (node (ref "S68") (pin "1") (pintype "passive"))
      (node (ref "S68a") (pin "1") (pintype "passive"))
      (node (ref "S68b") (pin "1") (pintype "passive"))
    )
    (net (code "90") (name "Net-(D69-PadK)") (class "Default")
      (node (ref "D69") (pin "K") (pintype "passive"))
      (node (ref "S69") (pin "1") (pintype "passive"))
    )
    (net (code "91") (name "Net-(D70-PadK)") (class "Default")
      (node (ref "D70") (pin "K") (pintype "passive"))
      (node (ref "S70") (pin "1") (pintype "passive"))
    )
    (net (code "92") (name "Net-(D71-PadK)") (class "Default")
      (node (ref "D71") (pin "K") (pintype "passive"))
      (node (ref "S71") (pin "1") (pintype "passive"))
    )
  )
)
